# ECAT0__IN.net
KiCad netlist of a schematic drawn in Altium Designer
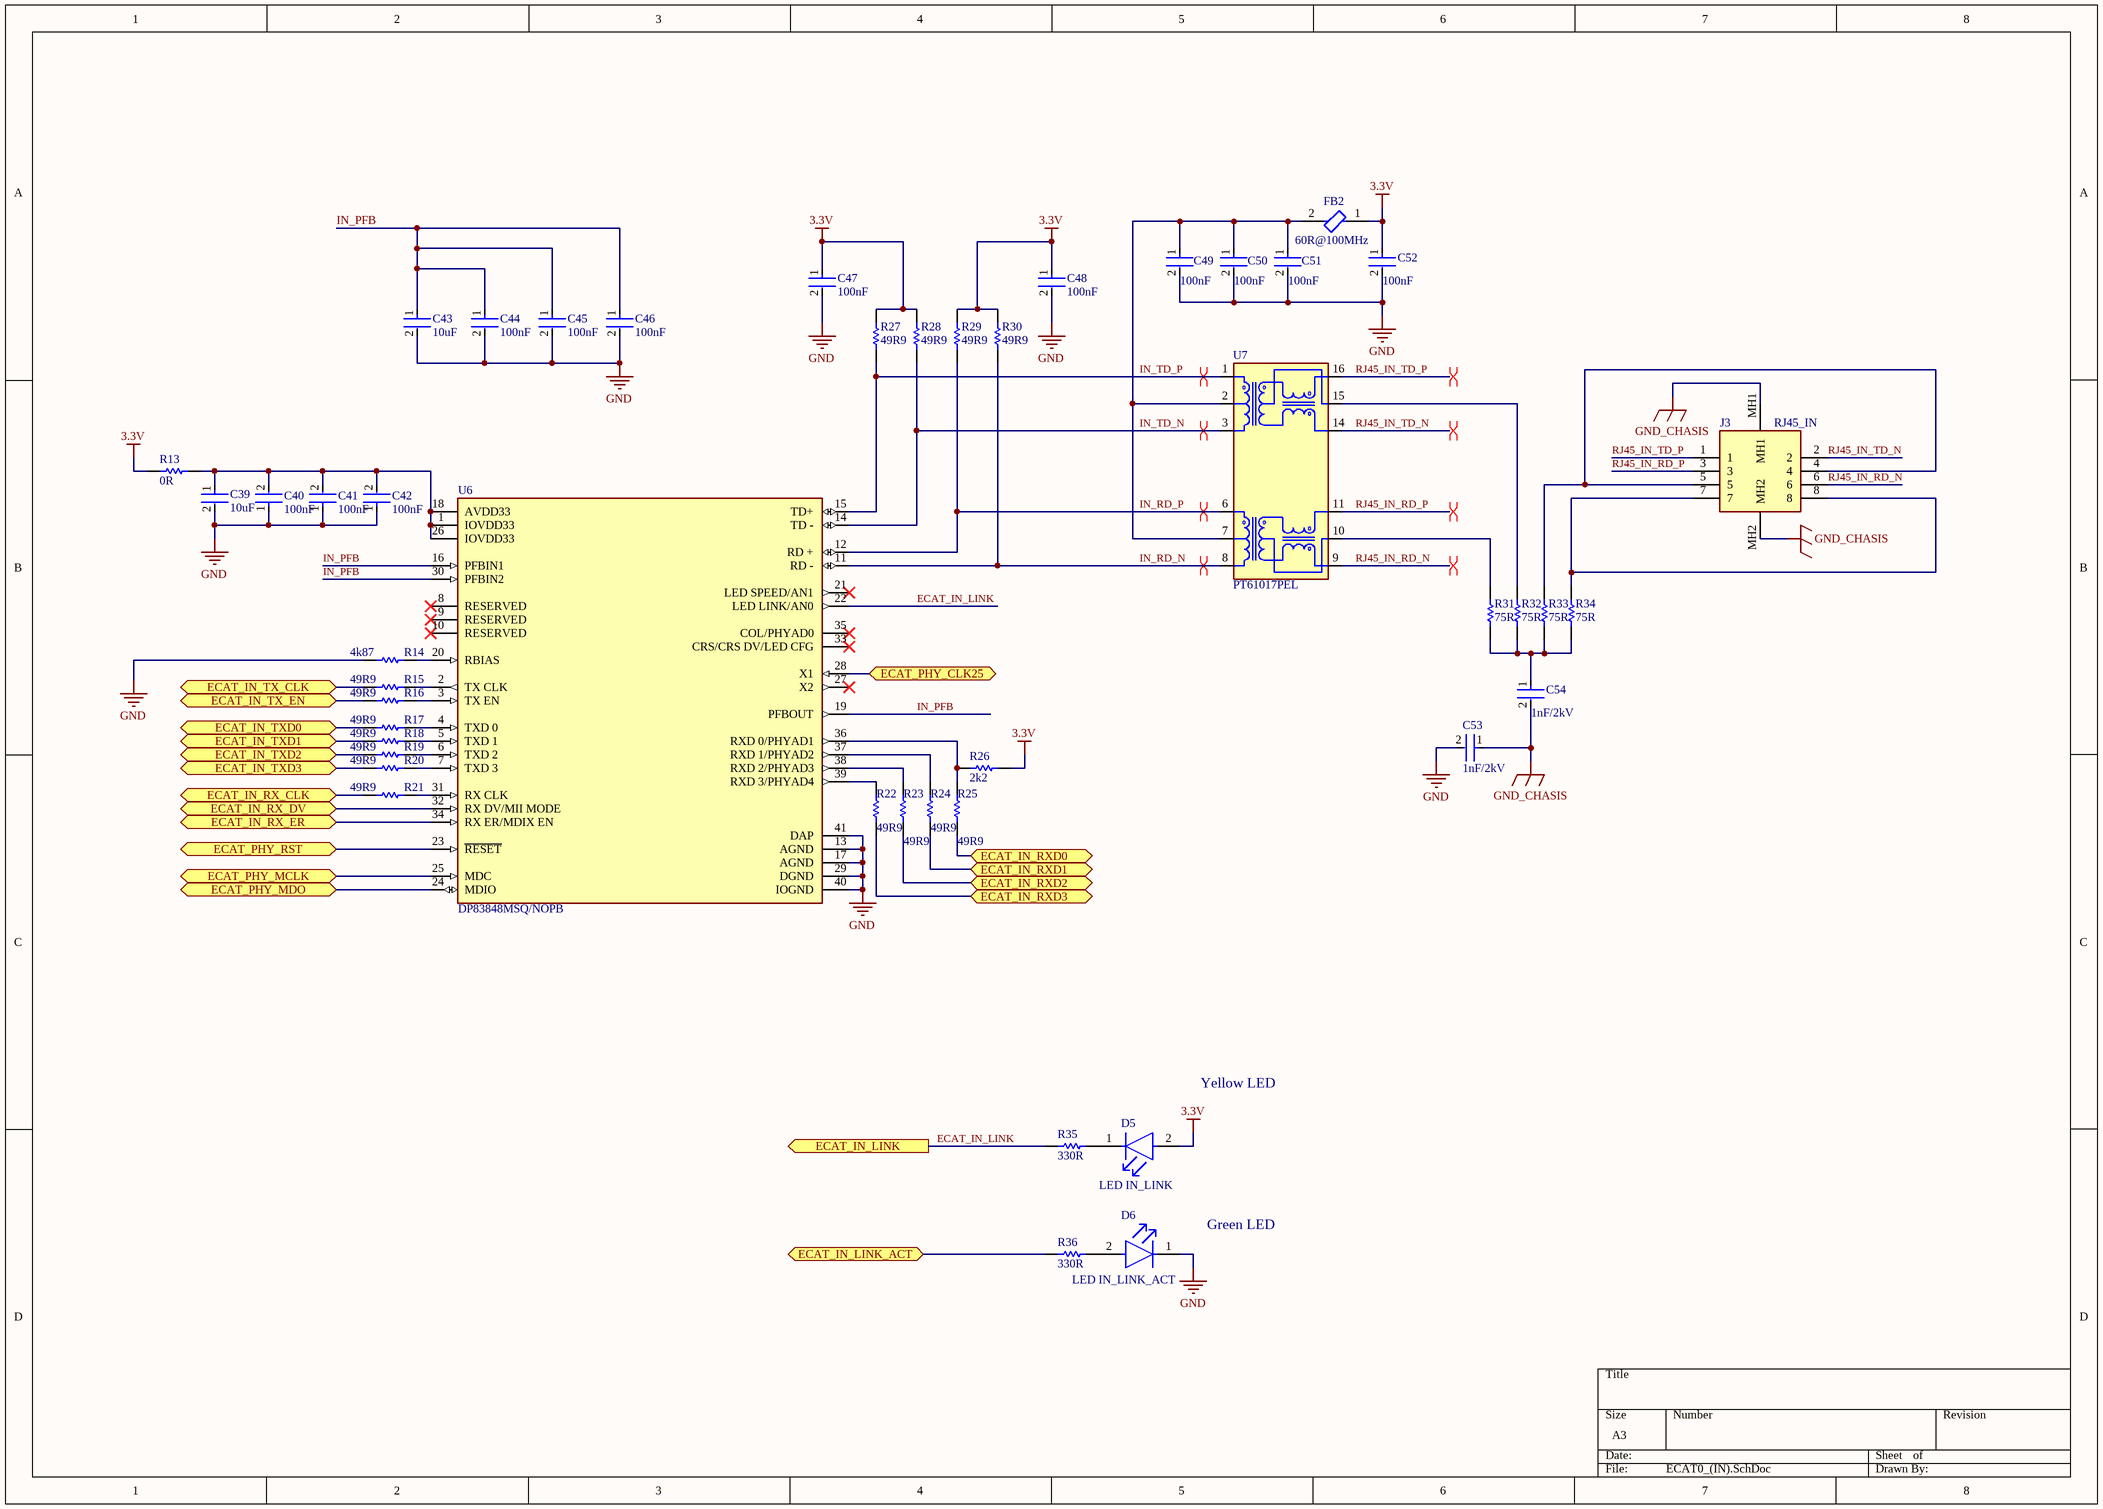
[diagram p0: ECAT0_(IN).SchDoc]

(export (version "E")
  (design (tool "Eeschema 10.0.6"))
  (components
    (comp (ref "C39")
      (value "10uF")
      (footprint "FP-C0805C-DN-MFG")
      (description "CAP CER 0.1UF 50V X7R 0805")
      (fields
        (field (name "MANUFACTURER PART NUMBER") "C0805C104K5RACTU")
        (field (name "MANUFACTURER") "KEMET")
      )
      (libsource (lib "Altium Content Vault") (part "b4654b650e69147ec39a6b967a45e02"))
    )
    (comp (ref "C40")
      (value "100nF")
      (footprint "FP-C0805C-DN-MFG")
      (description "CAP CER 0.1UF 50V X7R 0805")
      (fields
        (field (name "MANUFACTURER PART NUMBER") "C0805C104K5RACTU")
        (field (name "MANUFACTURER") "KEMET")
      )
      (libsource (lib "Altium Content Vault") (part "b4654b650e69147ec39a6b967a45e02"))
    )
    (comp (ref "C41")
      (value "100nF")
      (footprint "FP-C0805C-DN-MFG")
      (description "CAP CER 0.1UF 50V X7R 0805")
      (fields
        (field (name "MANUFACTURER PART NUMBER") "C0805C104K5RACTU")
        (field (name "MANUFACTURER") "KEMET")
      )
      (libsource (lib "Altium Content Vault") (part "b4654b650e69147ec39a6b967a45e02"))
    )
    (comp (ref "C42")
      (value "100nF")
      (footprint "FP-C0805C-DN-MFG")
      (description "CAP CER 0.1UF 50V X7R 0805")
      (fields
        (field (name "MANUFACTURER PART NUMBER") "C0805C104K5RACTU")
        (field (name "MANUFACTURER") "KEMET")
      )
      (libsource (lib "Altium Content Vault") (part "b4654b650e69147ec39a6b967a45e02"))
    )
    (comp (ref "C43")
      (value "10uF")
      (footprint "FP-C0805C-DN-MFG")
      (description "CAP CER 0.1UF 50V X7R 0805")
      (fields
        (field (name "MANUFACTURER PART NUMBER") "C0805C104K5RACTU")
        (field (name "MANUFACTURER") "KEMET")
      )
      (libsource (lib "Altium Content Vault") (part "b4654b650e69147ec39a6b967a45e02"))
    )
    (comp (ref "C44")
      (value "100nF")
      (footprint "FP-C0805C-DN-MFG")
      (description "CAP CER 0.1UF 50V X7R 0805")
      (fields
        (field (name "MANUFACTURER PART NUMBER") "C0805C104K5RACTU")
        (field (name "MANUFACTURER") "KEMET")
      )
      (libsource (lib "Altium Content Vault") (part "b4654b650e69147ec39a6b967a45e02"))
    )
    (comp (ref "C45")
      (value "100nF")
      (footprint "FP-C0805C-DN-MFG")
      (description "CAP CER 0.1UF 50V X7R 0805")
      (fields
        (field (name "MANUFACTURER PART NUMBER") "C0805C104K5RACTU")
        (field (name "MANUFACTURER") "KEMET")
      )
      (libsource (lib "Altium Content Vault") (part "b4654b650e69147ec39a6b967a45e02"))
    )
    (comp (ref "C46")
      (value "100nF")
      (footprint "FP-C0805C-DN-MFG")
      (description "CAP CER 0.1UF 50V X7R 0805")
      (fields
        (field (name "MANUFACTURER PART NUMBER") "C0805C104K5RACTU")
        (field (name "MANUFACTURER") "KEMET")
      )
      (libsource (lib "Altium Content Vault") (part "b4654b650e69147ec39a6b967a45e02"))
    )
    (comp (ref "C47")
      (value "100nF")
      (footprint "FP-C0805C-DN-MFG")
      (description "CAP CER 0.1UF 50V X7R 0805")
      (fields
        (field (name "MANUFACTURER PART NUMBER") "C0805C104K5RACTU")
        (field (name "MANUFACTURER") "KEMET")
      )
      (libsource (lib "Altium Content Vault") (part "b4654b650e69147ec39a6b967a45e02"))
    )
    (comp (ref "C48")
      (value "100nF")
      (footprint "FP-C0805C-DN-MFG")
      (description "CAP CER 0.1UF 50V X7R 0805")
      (fields
        (field (name "MANUFACTURER PART NUMBER") "C0805C104K5RACTU")
        (field (name "MANUFACTURER") "KEMET")
      )
      (libsource (lib "Altium Content Vault") (part "b4654b650e69147ec39a6b967a45e02"))
    )
    (comp (ref "C49")
      (value "100nF")
      (footprint "FP-C0805C-DN-MFG")
      (description "CAP CER 0.1UF 50V X7R 0805")
      (fields
        (field (name "MANUFACTURER PART NUMBER") "C0805C104K5RACTU")
        (field (name "MANUFACTURER") "KEMET")
      )
      (libsource (lib "Altium Content Vault") (part "b4654b650e69147ec39a6b967a45e02"))
    )
    (comp (ref "C50")
      (value "100nF")
      (footprint "FP-C0805C-DN-MFG")
      (description "CAP CER 0.1UF 50V X7R 0805")
      (fields
        (field (name "MANUFACTURER PART NUMBER") "C0805C104K5RACTU")
        (field (name "MANUFACTURER") "KEMET")
      )
      (libsource (lib "Altium Content Vault") (part "b4654b650e69147ec39a6b967a45e02"))
    )
    (comp (ref "C51")
      (value "100nF")
      (footprint "FP-C0805C-DN-MFG")
      (description "CAP CER 0.1UF 50V X7R 0805")
      (fields
        (field (name "MANUFACTURER PART NUMBER") "C0805C104K5RACTU")
        (field (name "MANUFACTURER") "KEMET")
      )
      (libsource (lib "Altium Content Vault") (part "b4654b650e69147ec39a6b967a45e02"))
    )
    (comp (ref "C52")
      (value "100nF")
      (footprint "FP-C0805C-DN-MFG")
      (description "CAP CER 0.1UF 50V X7R 0805")
      (fields
        (field (name "MANUFACTURER PART NUMBER") "C0805C104K5RACTU")
        (field (name "MANUFACTURER") "KEMET")
      )
      (libsource (lib "Altium Content Vault") (part "b4654b650e69147ec39a6b967a45e02"))
    )
    (comp (ref "C53")
      (value "1nF/2kV")
      (footprint "FP-CC1206-0_3-1_45-IPC_C")
      (description "1nF/2kV/1206")
      (fields (field (name "TOLERANCE") "10%") (field (name "VOLTAGE") "2kV"))
      (libsource (lib "Altium Content Vault") (part "02cd4be3c70576c341d710602a673aa"))
    )
    (comp (ref "C54")
      (value "1nF/2kV")
      (footprint "FP-CC1206-0_3-1_45-IPC_C")
      (description "1nF/2kV/1206")
      (fields (field (name "TOLERANCE") "10%") (field (name "VOLTAGE") "2kV"))
      (libsource (lib "Altium Content Vault") (part "02cd4be3c70576c341d710602a673aa"))
    )
    (comp (ref "D5")
      (value "LED IN_LINK")
      (footprint "FP-LTST-C191GKT-MFG")
      (description "KPHD-1608LVSYCK")
      (libsource (lib "Altium Content Vault") (part "8706943c75ba83719d021d2fdc84c58"))
    )
    (comp (ref "D6")
      (value "LED IN_LINK_ACT")
      (footprint "FP-LTST-C191GKT-MFG")
      (description "KPHD-1608LVCGCK")
      (libsource (lib "Altium Content Vault") (part "8706943c75ba83719d021d2fdc84c58"))
    )
    (comp (ref "FB2")
      (value "60R@100MHz")
      (footprint "FP-BLM18-0_15-t0_8-IPC_B")
      (description "Chip Ferrite Bead, 0603, 60Ω @ 100MHz, 0.1Ω, , 1A")
      (fields (field (name "TOLERANCE") "25%"))
      (libsource (lib "Altium Content Vault") (part "5f30dd21d616792df468990f7003faa"))
    )
    (comp (ref "J3")
      (value "RJ45_IN")
      (footprint "438600010")
      (fields
        (field (name "MOUSER PART NUMBER") "538-43860-0010")
        (field (name "MANUFACTURER_PART_NUMBER") "43860-0010")
      )
      (libsource (lib "43860-0010_RJ45") (part "43860-0010"))
    )
    (comp (ref "R13")
      (value "0R")
      (footprint "RESC1609X50X30NL8T20")
      (description "0603")
      (fields (field (name "MANUFACTURER") "Vishay Semiconductor"))
      (libsource (lib "Altium Content Vault") (part "RES-2"))
    )
    (comp (ref "R14")
      (value "4k87")
      (footprint "RESC2013X50X30LL20T20")
      (description "0805")
      (fields (field (name "MANUFACTURER") "Vishay Dale") (field (name "PART NUMBER") "CRCW08050000Z0EA"))
      (libsource (lib "Altium Content Vault") (part "RES"))
    )
    (comp (ref "R15")
      (value "49R9")
      (footprint "RESC2013X50X30LL20T20")
      (description "0805")
      (fields (field (name "MANUFACTURER") "Vishay Dale") (field (name "PART NUMBER") "CRCW08050000Z0EA"))
      (libsource (lib "Altium Content Vault") (part "RES"))
    )
    (comp (ref "R16")
      (value "49R9")
      (footprint "RESC2013X50X30LL20T20")
      (description "0805")
      (fields (field (name "MANUFACTURER") "Vishay Dale") (field (name "PART NUMBER") "CRCW08050000Z0EA"))
      (libsource (lib "Altium Content Vault") (part "RES"))
    )
    (comp (ref "R17")
      (value "49R9")
      (footprint "RESC2013X50X30LL20T20")
      (description "0805")
      (fields (field (name "MANUFACTURER") "Vishay Dale") (field (name "PART NUMBER") "CRCW08050000Z0EA"))
      (libsource (lib "Altium Content Vault") (part "RES"))
    )
    (comp (ref "R18")
      (value "49R9")
      (footprint "RESC2013X50X30LL20T20")
      (description "0805")
      (fields (field (name "MANUFACTURER") "Vishay Dale") (field (name "PART NUMBER") "CRCW08050000Z0EA"))
      (libsource (lib "Altium Content Vault") (part "RES"))
    )
    (comp (ref "R19")
      (value "49R9")
      (footprint "RESC2013X50X30LL20T20")
      (description "0805")
      (fields (field (name "MANUFACTURER") "Vishay Dale") (field (name "PART NUMBER") "CRCW08050000Z0EA"))
      (libsource (lib "Altium Content Vault") (part "RES"))
    )
    (comp (ref "R20")
      (value "49R9")
      (footprint "RESC2013X50X30LL20T20")
      (description "0805")
      (fields (field (name "MANUFACTURER") "Vishay Dale") (field (name "PART NUMBER") "CRCW08050000Z0EA"))
      (libsource (lib "Altium Content Vault") (part "RES"))
    )
    (comp (ref "R21")
      (value "49R9")
      (footprint "RESC2013X50X30LL20T20")
      (description "0805")
      (fields (field (name "MANUFACTURER") "Vishay Dale") (field (name "PART NUMBER") "CRCW08050000Z0EA"))
      (libsource (lib "Altium Content Vault") (part "RES"))
    )
    (comp (ref "R22")
      (value "49R9")
      (footprint "RESC2013X50X30LL20T20")
      (description "0805")
      (fields (field (name "MANUFACTURER") "Vishay Dale") (field (name "PART NUMBER") "CRCW08050000Z0EA"))
      (libsource (lib "Altium Content Vault") (part "RES"))
    )
    (comp (ref "R23")
      (value "49R9")
      (footprint "RESC2013X50X30LL20T20")
      (description "0805")
      (fields (field (name "MANUFACTURER") "Vishay Dale") (field (name "PART NUMBER") "CRCW08050000Z0EA"))
      (libsource (lib "Altium Content Vault") (part "RES"))
    )
    (comp (ref "R24")
      (value "49R9")
      (footprint "RESC2013X50X30LL20T20")
      (description "0805")
      (fields (field (name "MANUFACTURER") "Vishay Dale") (field (name "PART NUMBER") "CRCW08050000Z0EA"))
      (libsource (lib "Altium Content Vault") (part "RES"))
    )
    (comp (ref "R25")
      (value "49R9")
      (footprint "RESC2013X50X30LL20T20")
      (description "0805")
      (fields (field (name "MANUFACTURER") "Vishay Dale") (field (name "PART NUMBER") "CRCW08050000Z0EA"))
      (libsource (lib "Altium Content Vault") (part "RES"))
    )
    (comp (ref "R26")
      (value "2k2")
      (footprint "RESC2013X50X30LL20T20")
      (description "0805")
      (fields (field (name "MANUFACTURER") "Vishay Dale") (field (name "PART NUMBER") "CRCW08050000Z0EA"))
      (libsource (lib "Altium Content Vault") (part "RES"))
    )
    (comp (ref "R27")
      (value "49R9")
      (footprint "RESC2013X50X30LL20T20")
      (description "0805")
      (fields (field (name "MANUFACTURER") "Vishay Dale") (field (name "PART NUMBER") "CRCW08050000Z0EA"))
      (libsource (lib "Altium Content Vault") (part "RES"))
    )
    (comp (ref "R28")
      (value "49R9")
      (footprint "RESC2013X50X30LL20T20")
      (description "0805")
      (fields (field (name "MANUFACTURER") "Vishay Dale") (field (name "PART NUMBER") "CRCW08050000Z0EA"))
      (libsource (lib "Altium Content Vault") (part "RES"))
    )
    (comp (ref "R29")
      (value "49R9")
      (footprint "RESC2013X50X30LL20T20")
      (description "0805")
      (fields (field (name "MANUFACTURER") "Vishay Dale") (field (name "PART NUMBER") "CRCW08050000Z0EA"))
      (libsource (lib "Altium Content Vault") (part "RES"))
    )
    (comp (ref "R30")
      (value "49R9")
      (footprint "RESC2013X50X30LL20T20")
      (description "0805")
      (fields (field (name "MANUFACTURER") "Vishay Dale") (field (name "PART NUMBER") "CRCW08050000Z0EA"))
      (libsource (lib "Altium Content Vault") (part "RES"))
    )
    (comp (ref "R31")
      (value "75R")
      (footprint "RESC2013X50X30LL20T20")
      (description "0805")
      (fields (field (name "MANUFACTURER") "Vishay Dale") (field (name "PART NUMBER") "CRCW08050000Z0EA"))
      (libsource (lib "Altium Content Vault") (part "RES"))
    )
    (comp (ref "R32")
      (value "75R")
      (footprint "RESC2013X50X30LL20T20")
      (description "0805")
      (fields (field (name "MANUFACTURER") "Vishay Dale") (field (name "PART NUMBER") "CRCW08050000Z0EA"))
      (libsource (lib "Altium Content Vault") (part "RES"))
    )
    (comp (ref "R33")
      (value "75R")
      (footprint "RESC2013X50X30LL20T20")
      (description "0805")
      (fields (field (name "MANUFACTURER") "Vishay Dale") (field (name "PART NUMBER") "CRCW08050000Z0EA"))
      (libsource (lib "Altium Content Vault") (part "RES"))
    )
    (comp (ref "R34")
      (value "75R")
      (footprint "RESC2013X50X30LL20T20")
      (description "0805")
      (fields (field (name "MANUFACTURER") "Vishay Dale") (field (name "PART NUMBER") "CRCW08050000Z0EA"))
      (libsource (lib "Altium Content Vault") (part "RES"))
    )
    (comp (ref "R35")
      (value "330R")
      (footprint "RESC2013X50X30LL20T20")
      (description "0805")
      (fields (field (name "MANUFACTURER") "Vishay Dale") (field (name "PART NUMBER") "CRCW08050000Z0EA"))
      (libsource (lib "Altium Content Vault") (part "RES"))
    )
    (comp (ref "R36")
      (value "330R")
      (footprint "RESC2013X50X30LL20T20")
      (description "0805")
      (fields (field (name "MANUFACTURER") "Vishay Dale") (field (name "PART NUMBER") "CRCW08050000Z0EA"))
      (libsource (lib "Altium Content Vault") (part "RES"))
    )
    (comp (ref "U6")
      (value "DP83848MSQ/NOPB")
      (footprint "FP-RTA0040A-IPC_B")
      (description "IC TRANSCEIVER 1/1 40WQFN")
      (libsource (lib "Altium Content Vault") (part "3c06b58cd6473fc695b5b7b70754a9c"))
    )
    (comp (ref "U7")
      (value "PT61017PEL")
      (footprint "PT61017PEL")
      (description "350 µH LAN 10/100 Base-T Pulse Transformer 1CT:1CT Surface Mount\r\n\r\nPT61017PEL")
      (fields (field (name "MF") "Bourns"))
      (libsource (lib "OTHER") (part "PT61017PEL"))
    )
  )
  (nets
    (net (code "1") (name "/ECAT_IN_LINK") (class "Default")
      (node (ref "R35") (pin "1") (pinfunction "1_1") (pintype "passive"))
      (node (ref "U6") (pin "22") (pinfunction "LED_LINK/AN0_22") (pintype "output"))
    )
    (net (code "2") (name "/ECAT_IN_LINK_ACT") (class "Default")
      (node (ref "R36") (pin "1") (pinfunction "1_1") (pintype "passive"))
    )
    (net (code "3") (name "/ECAT_IN_RXD0") (class "Default")
      (node (ref "R25") (pin "1") (pinfunction "1_1") (pintype "passive"))
    )
    (net (code "4") (name "/ECAT_IN_RXD1") (class "Default")
      (node (ref "R24") (pin "1") (pinfunction "1_1") (pintype "passive"))
    )
    (net (code "5") (name "/ECAT_IN_RXD2") (class "Default")
      (node (ref "R23") (pin "1") (pinfunction "1_1") (pintype "passive"))
    )
    (net (code "6") (name "/ECAT_IN_RXD3") (class "Default")
      (node (ref "R22") (pin "1") (pinfunction "1_1") (pintype "passive"))
    )
    (net (code "7") (name "/ECAT_IN_RX_CLK") (class "Default")
      (node (ref "R21") (pin "1") (pinfunction "1_1") (pintype "passive"))
    )
    (net (code "8") (name "/ECAT_IN_RX_DV") (class "Default")
      (node (ref "U6") (pin "32") (pinfunction "RX_DV/MII_MODE_32") (pintype "input"))
    )
    (net (code "9") (name "/ECAT_IN_RX_ER") (class "Default")
      (node (ref "U6") (pin "34") (pinfunction "RX_ER/MDIX_EN_34") (pintype "input"))
    )
    (net (code "10") (name "/ECAT_IN_TXD0") (class "Default")
      (node (ref "R17") (pin "1") (pinfunction "1_1") (pintype "passive"))
    )
    (net (code "11") (name "/ECAT_IN_TXD1") (class "Default")
      (node (ref "R18") (pin "1") (pinfunction "1_1") (pintype "passive"))
    )
    (net (code "12") (name "/ECAT_IN_TXD2") (class "Default")
      (node (ref "R19") (pin "1") (pinfunction "1_1") (pintype "passive"))
    )
    (net (code "13") (name "/ECAT_IN_TXD3") (class "Default")
      (node (ref "R20") (pin "1") (pinfunction "1_1") (pintype "passive"))
    )
    (net (code "14") (name "/ECAT_IN_TX_CLK") (class "Default")
      (node (ref "R15") (pin "1") (pinfunction "1_1") (pintype "passive"))
    )
    (net (code "15") (name "/ECAT_IN_TX_EN") (class "Default")
      (node (ref "R16") (pin "1") (pinfunction "1_1") (pintype "passive"))
    )
    (net (code "16") (name "/ECAT_PHY_CLK25") (class "Default")
      (node (ref "U6") (pin "28") (pinfunction "X1_28") (pintype "input"))
    )
    (net (code "17") (name "/ECAT_PHY_MCLK") (class "Default")
      (node (ref "U6") (pin "25") (pinfunction "MDC_25") (pintype "input"))
    )
    (net (code "18") (name "/ECAT_PHY_MDO") (class "Default")
      (node (ref "U6") (pin "24") (pinfunction "MDIO_24") (pintype "bidirectional"))
    )
    (net (code "19") (name "/ECAT_PHY_RST") (class "Default")
      (node (ref "U6") (pin "23") (pinfunction "~{RESET}_23") (pintype "input"))
    )
    (net (code "20") (name "/IN_PFB") (class "Default")
      (node (ref "C43") (pin "1") (pinfunction "1_1") (pintype "passive"))
      (node (ref "C44") (pin "1") (pinfunction "1_1") (pintype "passive"))
      (node (ref "C45") (pin "1") (pinfunction "1_1") (pintype "passive"))
      (node (ref "C46") (pin "1") (pinfunction "1_1") (pintype "passive"))
      (node (ref "U6") (pin "16") (pinfunction "PFBIN1_16") (pintype "input"))
      (node (ref "U6") (pin "19") (pinfunction "PFBOUT_19") (pintype "output"))
      (node (ref "U6") (pin "30") (pinfunction "PFBIN2_30") (pintype "input"))
    )
    (net (code "21") (name "/IN_RD_N") (class "Default")
      (node (ref "R30") (pin "1") (pinfunction "1_1") (pintype "passive"))
      (node (ref "U6") (pin "11") (pinfunction "RD_-_11") (pintype "bidirectional"))
      (node (ref "U7") (pin "8") (pinfunction "8_8") (pintype "passive"))
    )
    (net (code "22") (name "/IN_RD_P") (class "Default")
      (node (ref "R29") (pin "1") (pinfunction "1_1") (pintype "passive"))
      (node (ref "U6") (pin "12") (pinfunction "RD_+_12") (pintype "bidirectional"))
      (node (ref "U7") (pin "6") (pinfunction "6_6") (pintype "passive"))
    )
    (net (code "23") (name "/IN_TD_N") (class "Default")
      (node (ref "R28") (pin "1") (pinfunction "1_1") (pintype "passive"))
      (node (ref "U6") (pin "14") (pinfunction "TD_-_14") (pintype "bidirectional"))
      (node (ref "U7") (pin "3") (pinfunction "3_3") (pintype "passive"))
    )
    (net (code "24") (name "/IN_TD_P") (class "Default")
      (node (ref "R27") (pin "1") (pinfunction "1_1") (pintype "passive"))
      (node (ref "U6") (pin "15") (pinfunction "TD+_15") (pintype "bidirectional"))
      (node (ref "U7") (pin "1") (pinfunction "1_1") (pintype "passive"))
    )
    (net (code "25") (name "/RJ45_IN_RD_N") (class "Default")
      (node (ref "J3") (pin "6") (pinfunction "6_6") (pintype "passive"))
      (node (ref "U7") (pin "9") (pinfunction "9_9") (pintype "passive"))
    )
    (net (code "26") (name "/RJ45_IN_RD_P") (class "Default")
      (node (ref "J3") (pin "3") (pinfunction "3_3") (pintype "passive"))
      (node (ref "U7") (pin "11") (pinfunction "11_11") (pintype "passive"))
    )
    (net (code "27") (name "/RJ45_IN_TD_N") (class "Default")
      (node (ref "J3") (pin "2") (pinfunction "2_2") (pintype "passive"))
      (node (ref "U7") (pin "14") (pinfunction "14_14") (pintype "passive"))
    )
    (net (code "28") (name "/RJ45_IN_TD_P") (class "Default")
      (node (ref "J3") (pin "1") (pinfunction "1_1") (pintype "passive"))
      (node (ref "U7") (pin "16") (pinfunction "16_16") (pintype "passive"))
    )
    (net (code "29") (name "3.3V") (class "Default")
      (node (ref "C47") (pin "1") (pinfunction "1_1") (pintype "passive"))
      (node (ref "C48") (pin "1") (pinfunction "1_1") (pintype "passive"))
      (node (ref "C52") (pin "1") (pinfunction "1_1") (pintype "passive"))
      (node (ref "D5") (pin "2") (pinfunction "A_2") (pintype "passive"))
      (node (ref "FB2") (pin "1") (pinfunction "1_1") (pintype "passive"))
      (node (ref "R13") (pin "2") (pinfunction "2_2") (pintype "passive"))
      (node (ref "R26") (pin "1") (pinfunction "1_1") (pintype "passive"))
      (node (ref "R27") (pin "2") (pinfunction "2_2") (pintype "passive"))
      (node (ref "R28") (pin "2") (pinfunction "2_2") (pintype "passive"))
      (node (ref "R29") (pin "2") (pinfunction "2_2") (pintype "passive"))
      (node (ref "R30") (pin "2") (pinfunction "2_2") (pintype "passive"))
    )
    (net (code "30") (name "GND") (class "Default")
      (node (ref "C39") (pin "2") (pinfunction "2_2") (pintype "passive"))
      (node (ref "C40") (pin "1") (pinfunction "1_1") (pintype "passive"))
      (node (ref "C41") (pin "1") (pinfunction "1_1") (pintype "passive"))
      (node (ref "C42") (pin "1") (pinfunction "1_1") (pintype "passive"))
      (node (ref "C43") (pin "2") (pinfunction "2_2") (pintype "passive"))
      (node (ref "C44") (pin "2") (pinfunction "2_2") (pintype "passive"))
      (node (ref "C45") (pin "2") (pinfunction "2_2") (pintype "passive"))
      (node (ref "C46") (pin "2") (pinfunction "2_2") (pintype "passive"))
      (node (ref "C47") (pin "2") (pinfunction "2_2") (pintype "passive"))
      (node (ref "C48") (pin "2") (pinfunction "2_2") (pintype "passive"))
      (node (ref "C49") (pin "2") (pinfunction "2_2") (pintype "passive"))
      (node (ref "C50") (pin "2") (pinfunction "2_2") (pintype "passive"))
      (node (ref "C51") (pin "2") (pinfunction "2_2") (pintype "passive"))
      (node (ref "C52") (pin "2") (pinfunction "2_2") (pintype "passive"))
      (node (ref "C53") (pin "2") (pinfunction "2_2") (pintype "passive"))
      (node (ref "D6") (pin "1") (pinfunction "C_1") (pintype "passive"))
      (node (ref "R14") (pin "1") (pinfunction "1_1") (pintype "passive"))
      (node (ref "U6") (pin "13") (pinfunction "AGND_13") (pintype "power_in"))
      (node (ref "U6") (pin "17") (pinfunction "AGND_17") (pintype "power_in"))
      (node (ref "U6") (pin "29") (pinfunction "DGND_29") (pintype "power_in"))
      (node (ref "U6") (pin "40") (pinfunction "IOGND_40") (pintype "power_in"))
      (node (ref "U6") (pin "41") (pinfunction "DAP_41") (pintype "power_in"))
    )
    (net (code "31") (name "GND_CHASIS") (class "Default")
      (node (ref "C53") (pin "1") (pinfunction "1_1") (pintype "passive"))
      (node (ref "C54") (pin "2") (pinfunction "2_2") (pintype "passive"))
      (node (ref "J3") (pin "MH1") (pinfunction "MH1_MH1") (pintype "passive"))
      (node (ref "J3") (pin "MH2") (pinfunction "MH2_MH2") (pintype "passive"))
    )
    (net (code "32") (name "Net-(C49-Pad1)") (class "Default")
      (node (ref "C49") (pin "1") (pinfunction "1_1") (pintype "passive"))
      (node (ref "C50") (pin "1") (pinfunction "1_1") (pintype "passive"))
      (node (ref "C51") (pin "1") (pinfunction "1_1") (pintype "passive"))
      (node (ref "FB2") (pin "2") (pinfunction "2_2") (pintype "passive"))
      (node (ref "U7") (pin "2") (pinfunction "2_2") (pintype "passive"))
      (node (ref "U7") (pin "7") (pinfunction "7_7") (pintype "passive"))
    )
    (net (code "33") (name "Net-(C54-Pad1)") (class "Default")
      (node (ref "C54") (pin "1") (pinfunction "1_1") (pintype "passive"))
      (node (ref "R31") (pin "1") (pinfunction "1_1") (pintype "passive"))
      (node (ref "R32") (pin "1") (pinfunction "1_1") (pintype "passive"))
      (node (ref "R33") (pin "1") (pinfunction "1_1") (pintype "passive"))
      (node (ref "R34") (pin "1") (pinfunction "1_1") (pintype "passive"))
    )
    (net (code "34") (name "Net-(D5-C)") (class "Default")
      (node (ref "D5") (pin "1") (pinfunction "C_1") (pintype "passive"))
      (node (ref "R35") (pin "2") (pinfunction "2_2") (pintype "passive"))
    )
    (net (code "35") (name "Net-(D6-A)") (class "Default")
      (node (ref "D6") (pin "2") (pinfunction "A_2") (pintype "passive"))
      (node (ref "R36") (pin "2") (pinfunction "2_2") (pintype "passive"))
    )
    (net (code "36") (name "Net-(J3-Pad4)") (class "Default")
      (node (ref "J3") (pin "4") (pinfunction "4_4") (pintype "passive"))
      (node (ref "J3") (pin "5") (pinfunction "5_5") (pintype "passive"))
      (node (ref "R33") (pin "2") (pinfunction "2_2") (pintype "passive"))
    )
    (net (code "37") (name "Net-(J3-Pad7)") (class "Default")
      (node (ref "J3") (pin "7") (pinfunction "7_7") (pintype "passive"))
      (node (ref "J3") (pin "8") (pinfunction "8_8") (pintype "passive"))
      (node (ref "R34") (pin "2") (pinfunction "2_2") (pintype "passive"))
    )
    (net (code "38") (name "Net-(R31-Pad2)") (class "Default")
      (node (ref "R31") (pin "2") (pinfunction "2_2") (pintype "passive"))
      (node (ref "U7") (pin "10") (pinfunction "10_10") (pintype "passive"))
    )
    (net (code "39") (name "Net-(R32-Pad2)") (class "Default")
      (node (ref "R32") (pin "2") (pinfunction "2_2") (pintype "passive"))
      (node (ref "U7") (pin "15") (pinfunction "15_15") (pintype "passive"))
    )
    (net (code "40") (name "Net-(U6-AVDD33)") (class "Default")
      (node (ref "C39") (pin "1") (pinfunction "1_1") (pintype "passive"))
      (node (ref "C40") (pin "2") (pinfunction "2_2") (pintype "passive"))
      (node (ref "C41") (pin "2") (pinfunction "2_2") (pintype "passive"))
      (node (ref "C42") (pin "2") (pinfunction "2_2") (pintype "passive"))
      (node (ref "R13") (pin "1") (pinfunction "1_1") (pintype "passive"))
      (node (ref "U6") (pin "1") (pinfunction "IOVDD33_1") (pintype "power_in"))
      (node (ref "U6") (pin "18") (pinfunction "AVDD33_18") (pintype "power_in"))
      (node (ref "U6") (pin "26") (pinfunction "IOVDD33_26") (pintype "power_in"))
    )
    (net (code "41") (name "Net-(U6-RBIAS)") (class "Default")
      (node (ref "R14") (pin "2") (pinfunction "2_2") (pintype "passive"))
      (node (ref "U6") (pin "20") (pinfunction "RBIAS_20") (pintype "input"))
    )
    (net (code "42") (name "Net-(U6-RXD_0{slash}PHYAD1)") (class "Default")
      (node (ref "R25") (pin "2") (pinfunction "2_2") (pintype "passive"))
      (node (ref "R26") (pin "2") (pinfunction "2_2") (pintype "passive"))
      (node (ref "U6") (pin "36") (pinfunction "RXD_0/PHYAD1_36") (pintype "output"))
    )
    (net (code "43") (name "Net-(U6-RXD_1{slash}PHYAD2)") (class "Default")
      (node (ref "R24") (pin "2") (pinfunction "2_2") (pintype "passive"))
      (node (ref "U6") (pin "37") (pinfunction "RXD_1/PHYAD2_37") (pintype "output"))
    )
    (net (code "44") (name "Net-(U6-RXD_2{slash}PHYAD3)") (class "Default")
      (node (ref "R23") (pin "2") (pinfunction "2_2") (pintype "passive"))
      (node (ref "U6") (pin "38") (pinfunction "RXD_2/PHYAD3_38") (pintype "output"))
    )
    (net (code "45") (name "Net-(U6-RXD_3{slash}PHYAD4)") (class "Default")
      (node (ref "R22") (pin "2") (pinfunction "2_2") (pintype "passive"))
      (node (ref "U6") (pin "39") (pinfunction "RXD_3/PHYAD4_39") (pintype "output"))
    )
    (net (code "46") (name "Net-(U6-RX_CLK)") (class "Default")
      (node (ref "R21") (pin "2") (pinfunction "2_2") (pintype "passive"))
      (node (ref "U6") (pin "31") (pinfunction "RX_CLK_31") (pintype "input"))
    )
    (net (code "47") (name "Net-(U6-TXD_0)") (class "Default")
      (node (ref "R17") (pin "2") (pinfunction "2_2") (pintype "passive"))
      (node (ref "U6") (pin "4") (pinfunction "TXD_0_4") (pintype "input"))
    )
    (net (code "48") (name "Net-(U6-TXD_1)") (class "Default")
      (node (ref "R18") (pin "2") (pinfunction "2_2") (pintype "passive"))
      (node (ref "U6") (pin "5") (pinfunction "TXD_1_5") (pintype "input"))
    )
    (net (code "49") (name "Net-(U6-TXD_2)") (class "Default")
      (node (ref "R19") (pin "2") (pinfunction "2_2") (pintype "passive"))
      (node (ref "U6") (pin "6") (pinfunction "TXD_2_6") (pintype "input"))
    )
    (net (code "50") (name "Net-(U6-TXD_3)") (class "Default")
      (node (ref "R20") (pin "2") (pinfunction "2_2") (pintype "passive"))
      (node (ref "U6") (pin "7") (pinfunction "TXD_3_7") (pintype "input"))
    )
    (net (code "51") (name "Net-(U6-TX_CLK)") (class "Default")
      (node (ref "R15") (pin "2") (pinfunction "2_2") (pintype "passive"))
      (node (ref "U6") (pin "2") (pinfunction "TX_CLK_2") (pintype "output"))
    )
    (net (code "52") (name "Net-(U6-TX_EN)") (class "Default")
      (node (ref "R16") (pin "2") (pinfunction "2_2") (pintype "passive"))
      (node (ref "U6") (pin "3") (pinfunction "TX_EN_3") (pintype "input"))
    )
    (net (code "53") (name "unconnected-(U6-COL{slash}PHYAD0-Pad35)") (class "Default")
      (node (ref "U6") (pin "35") (pinfunction "COL/PHYAD0_35") (pintype "passive+no_connect"))
    )
    (net (code "54") (name "unconnected-(U6-CRS{slash}CRS_DV{slash}LED_CFG-Pad33)") (class "Default")
      (node (ref "U6") (pin "33") (pinfunction "CRS/CRS_DV/LED_CFG_33") (pintype "passive+no_connect"))
    )
    (net (code "55") (name "unconnected-(U6-LED_SPEED{slash}AN1-Pad21)") (class "Default")
      (node (ref "U6") (pin "21") (pinfunction "LED_SPEED/AN1_21") (pintype "output+no_connect"))
    )
    (net (code "56") (name "unconnected-(U6-RESERVED-Pad8)") (class "Default")
      (node (ref "U6") (pin "8") (pinfunction "RESERVED_8") (pintype "passive+no_connect"))
    )
    (net (code "57") (name "unconnected-(U6-RESERVED-Pad9)") (class "Default")
      (node (ref "U6") (pin "9") (pinfunction "RESERVED_9") (pintype "passive+no_connect"))
    )
    (net (code "58") (name "unconnected-(U6-RESERVED-Pad10)") (class "Default")
      (node (ref "U6") (pin "10") (pinfunction "RESERVED_10") (pintype "passive+no_connect"))
    )
    (net (code "59") (name "unconnected-(U6-X2-Pad27)") (class "Default")
      (node (ref "U6") (pin "27") (pinfunction "X2_27") (pintype "output+no_connect"))
    )
  )
)
